# EPS.net
KiCad netlist of a schematic drawn in EAGLE
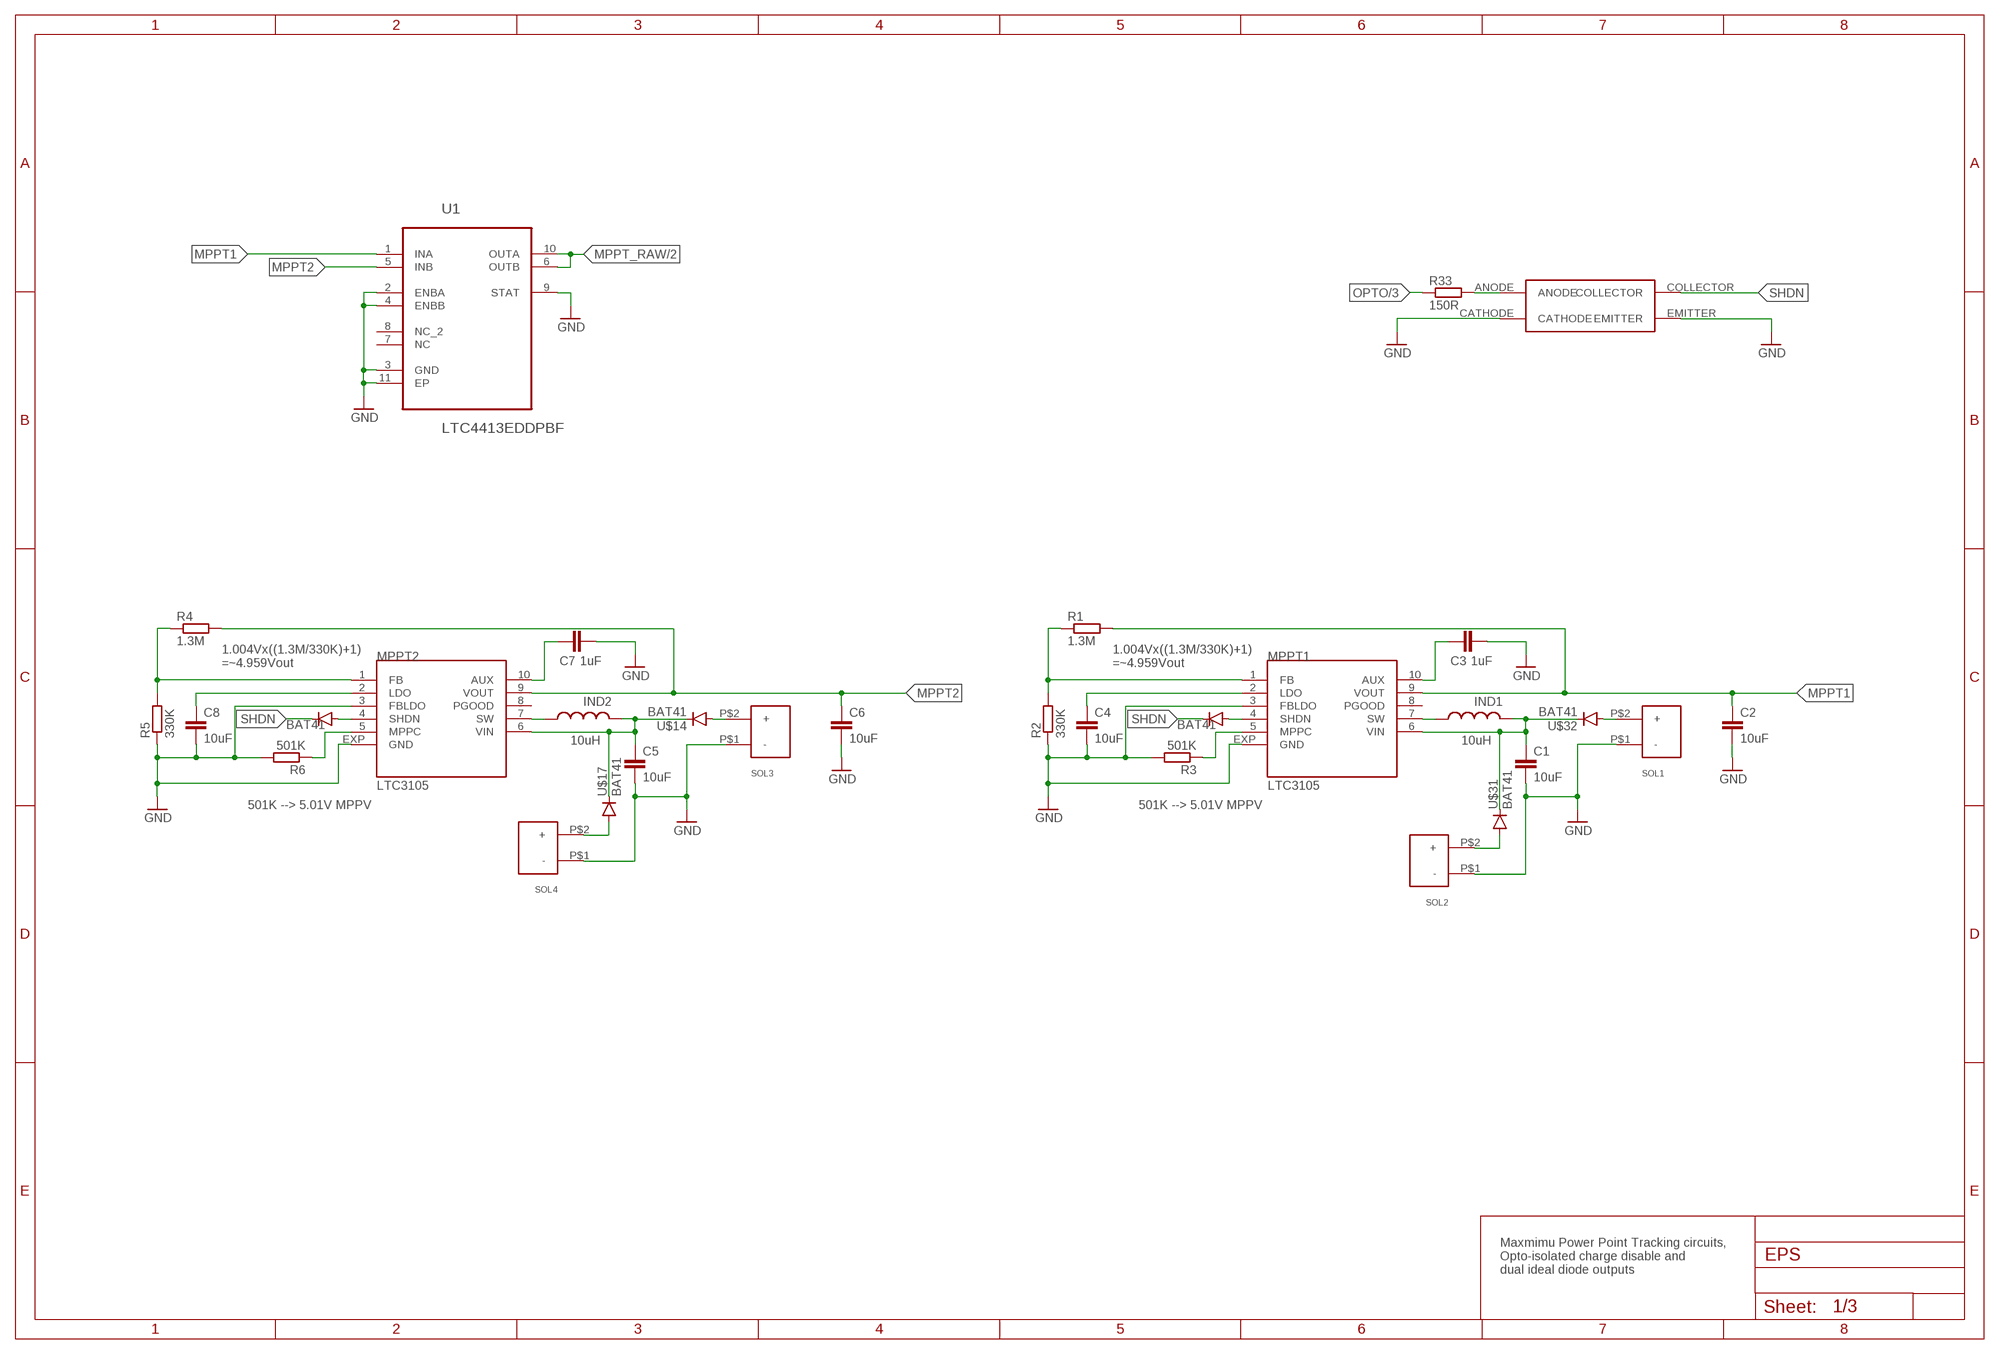
[diagram p0: schematic, sheet 1]
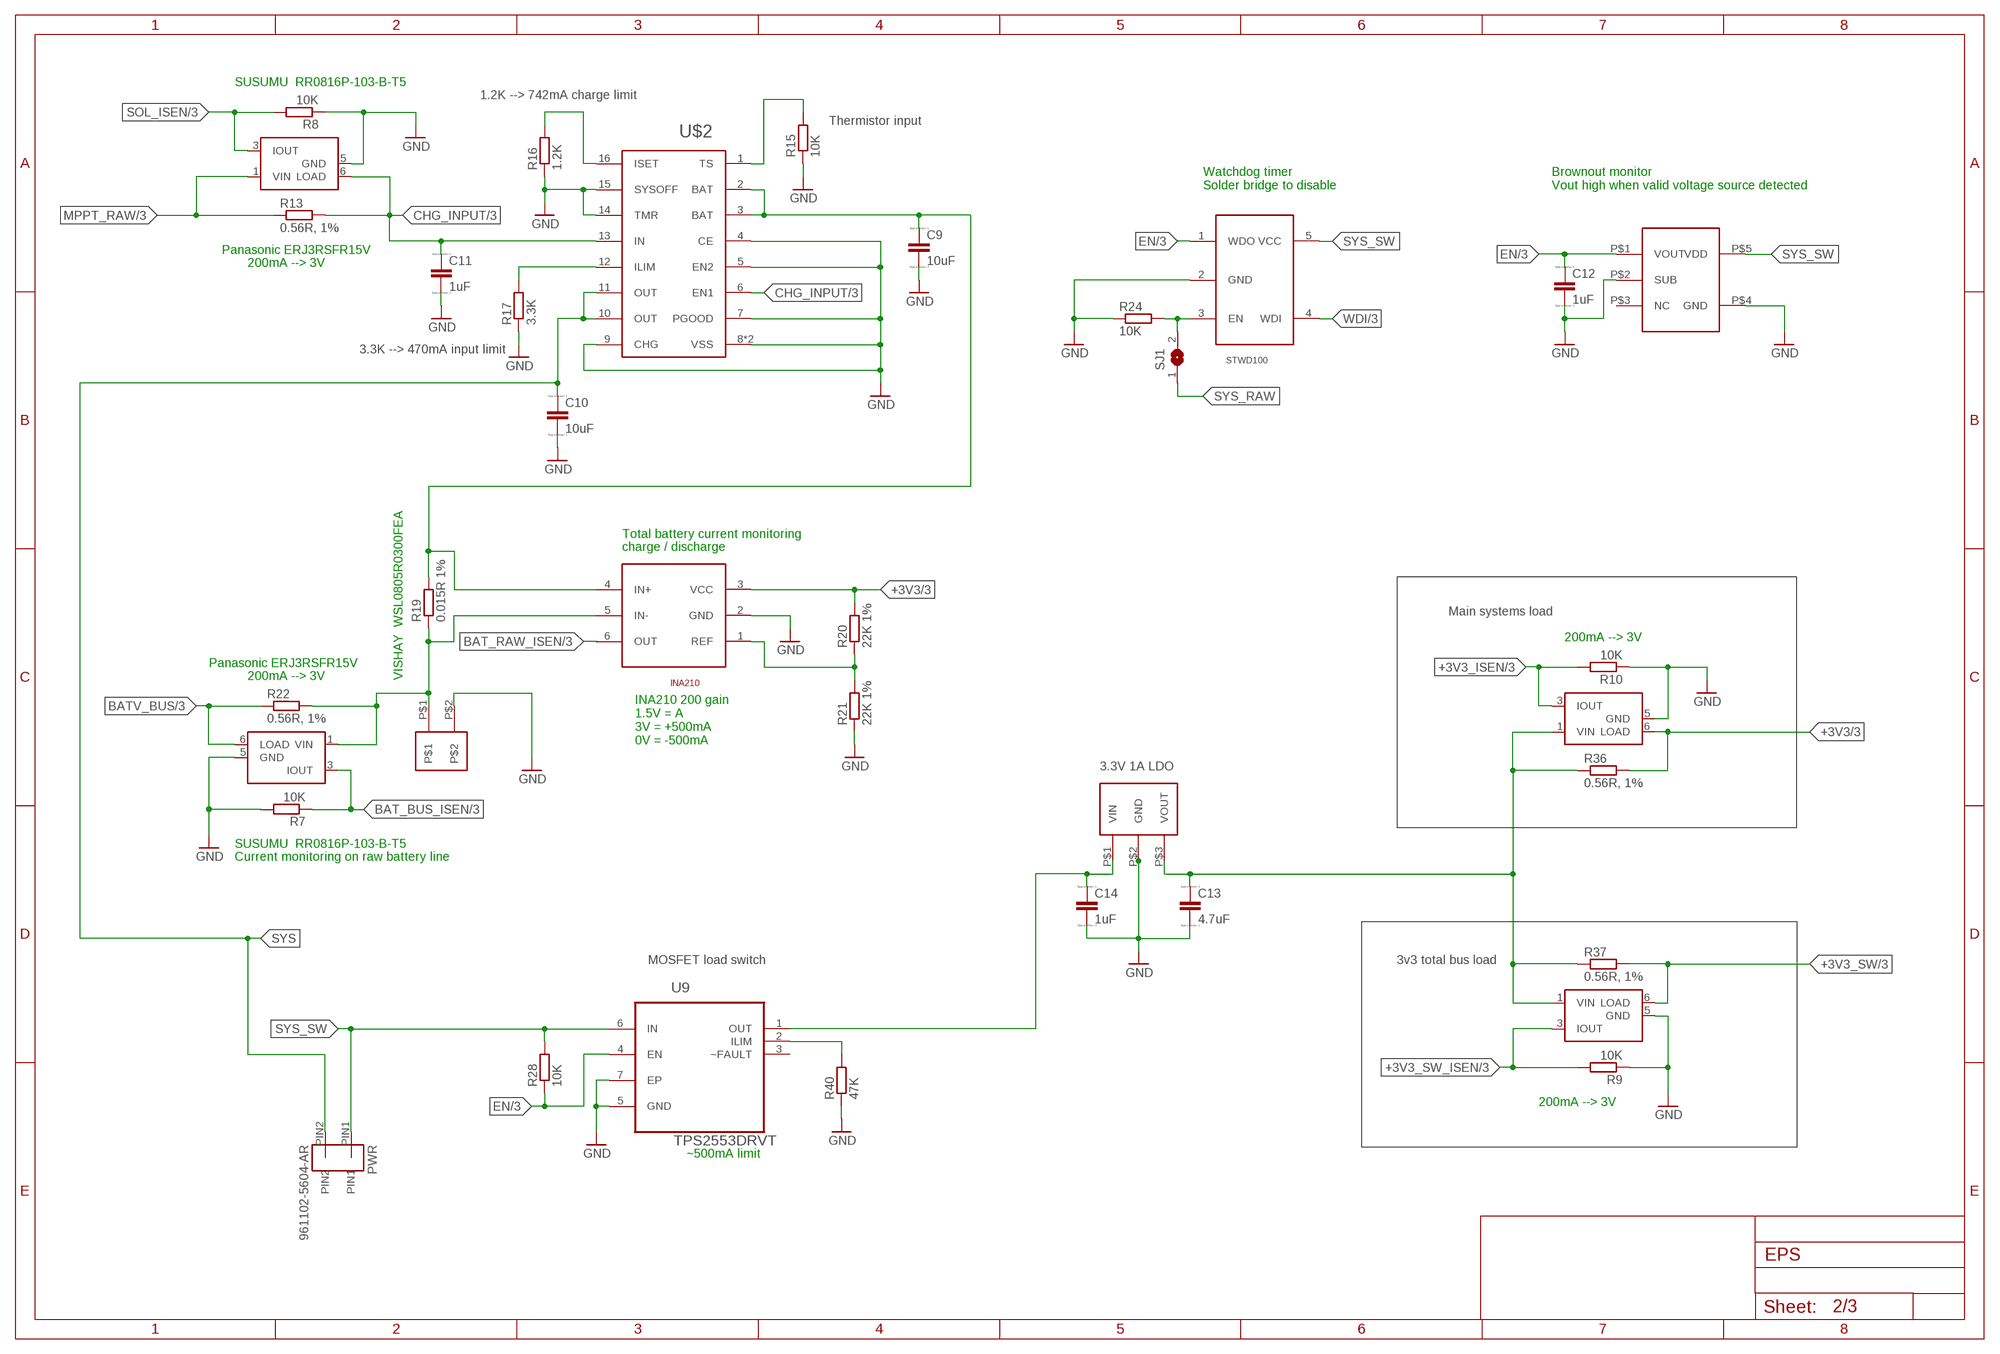
[diagram p1: schematic, sheet 2]
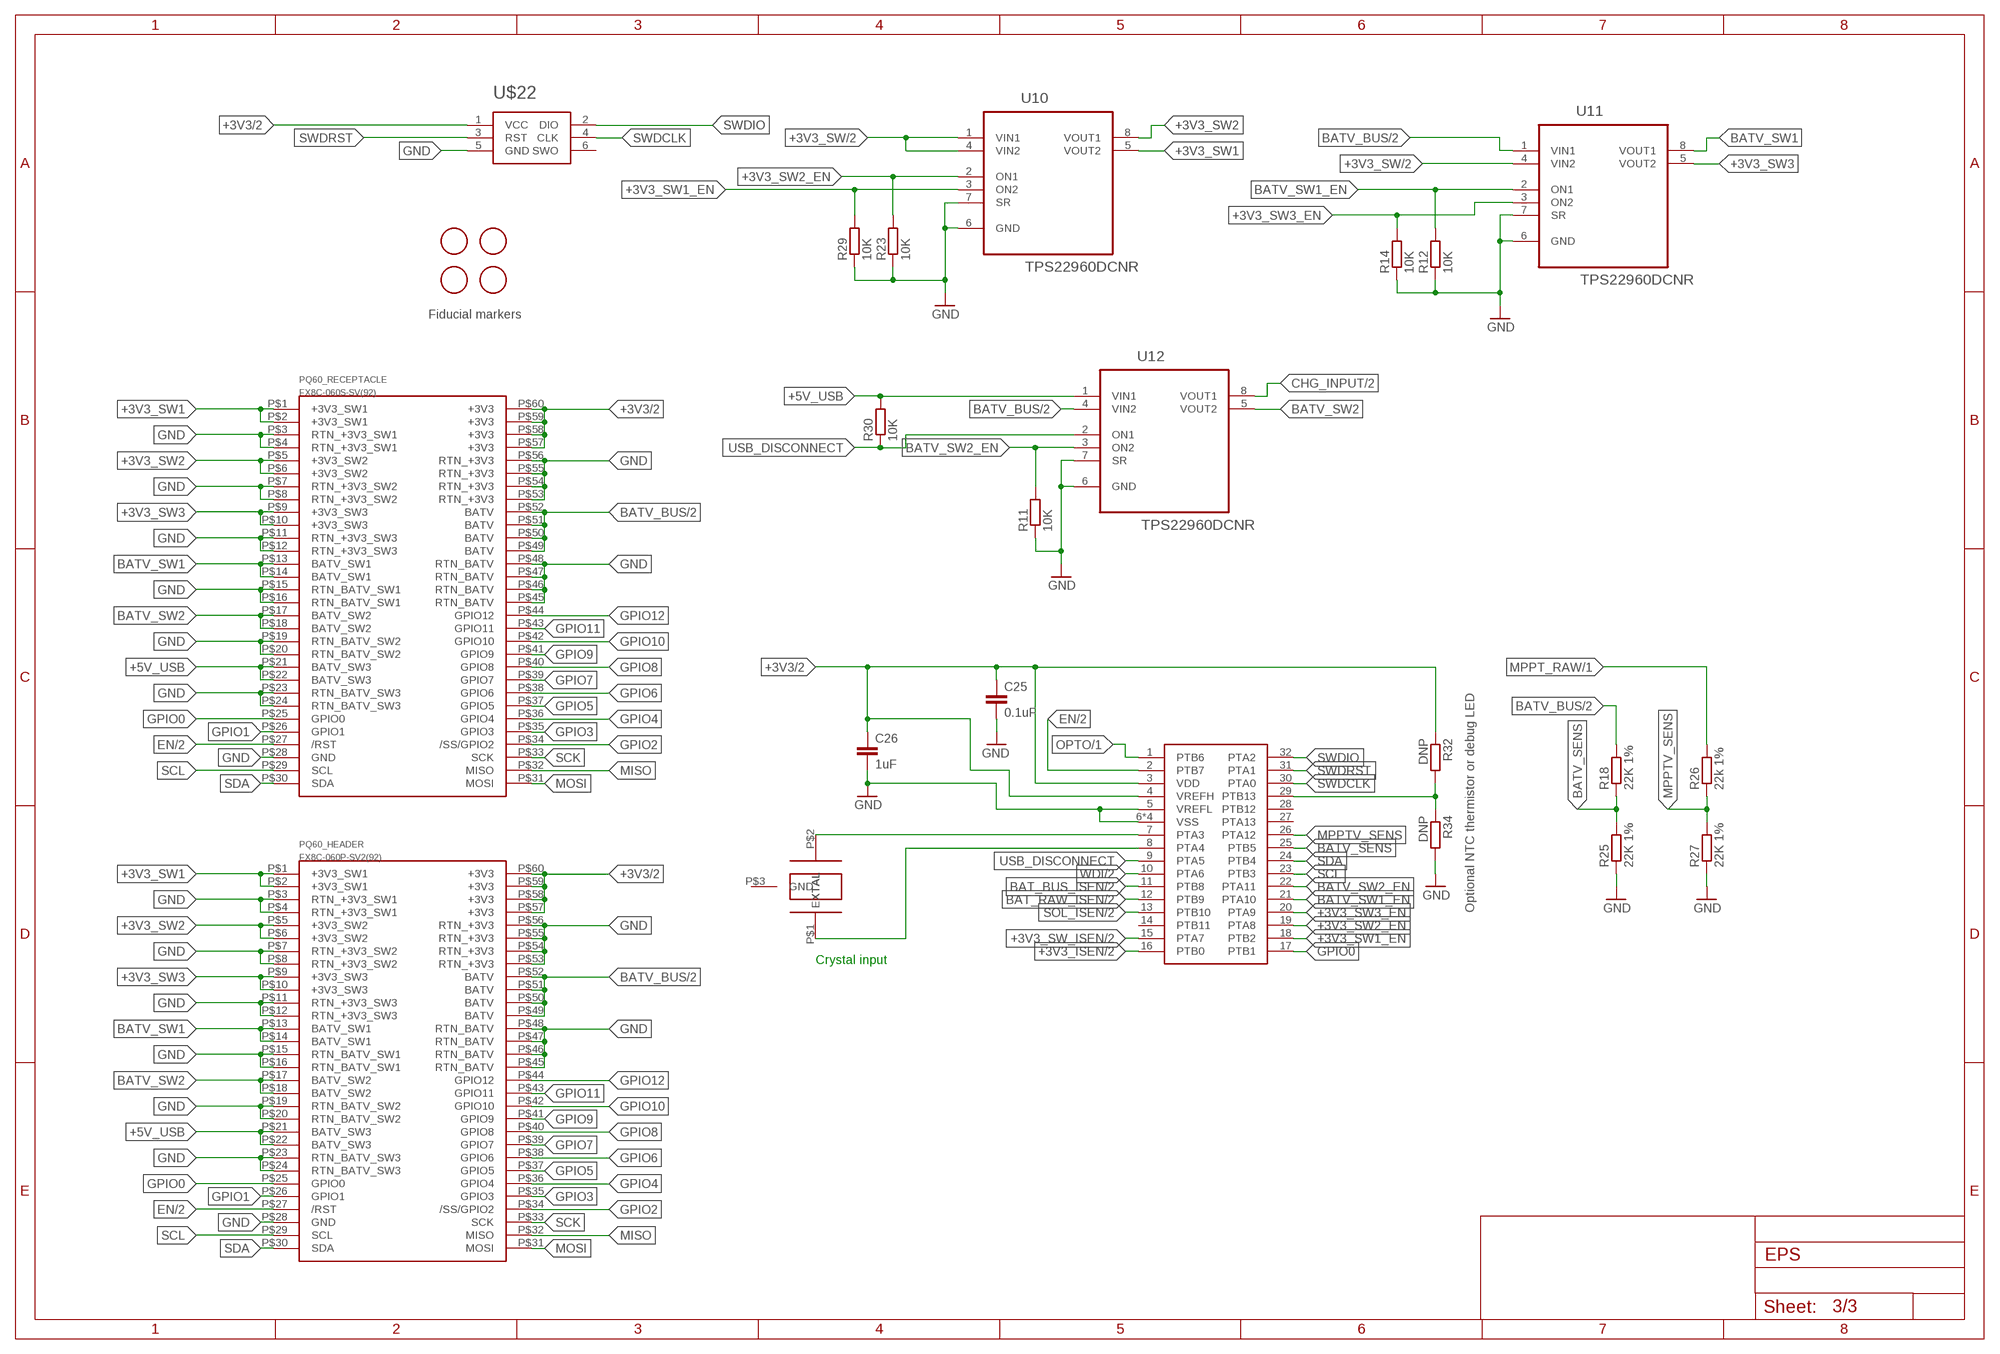
[diagram p2: schematic, sheet 3]

(export (version "E")
  (design (tool "Eeschema 10.0.6"))
  (components
    (comp (ref "C9")
      (value "10uF")
      (footprint "eagle-import:C0805")
      (libsource (lib "eagle-import") (part "C-EUC0805"))
    )
    (comp (ref "C10")
      (value "10uF")
      (footprint "eagle-import:C0805")
      (libsource (lib "eagle-import") (part "C-EUC0805"))
    )
    (comp (ref "C11")
      (value "1uF")
      (footprint "eagle-import:C0603")
      (libsource (lib "eagle-import") (part "C-EUC0603"))
    )
    (comp (ref "C12")
      (value "1uF")
      (footprint "eagle-import:C0603")
      (libsource (lib "eagle-import") (part "C-EUC0603"))
    )
    (comp (ref "C13")
      (value "4.7uF")
      (footprint "eagle-import:C0805")
      (libsource (lib "eagle-import") (part "C-EUC0805"))
    )
    (comp (ref "C14")
      (value "1uF")
      (footprint "eagle-import:C0603")
      (libsource (lib "eagle-import") (part "C-EUC0603"))
    )
    (comp (ref "INA210")
      (value "INA211A")
      (footprint "eagle-import:SC-70")
      (libsource (lib "eagle-import") (part "INA211A"))
    )
    (comp (ref "PWR")
      (value "961102-5604-AR")
      (footprint "eagle-import:961102-5604-AR")
      (libsource (lib "eagle-import") (part "961102-5604-AR"))
    )
    (comp (ref "R7")
      (value "10K")
      (footprint "eagle-import:R0402")
      (libsource (lib "eagle-import") (part "R-EU_R0402"))
    )
    (comp (ref "R8")
      (value "10K")
      (footprint "eagle-import:R0402")
      (libsource (lib "eagle-import") (part "R-EU_R0402"))
    )
    (comp (ref "R9")
      (value "10K")
      (footprint "eagle-import:R0402")
      (libsource (lib "eagle-import") (part "R-EU_R0402"))
    )
    (comp (ref "R10")
      (value "10K")
      (footprint "eagle-import:R0402")
      (libsource (lib "eagle-import") (part "R-EU_R0402"))
    )
    (comp (ref "R13")
      (value "0.56R, 1%")
      (footprint "eagle-import:R0603")
      (libsource (lib "eagle-import") (part "R-EU_R0603"))
    )
    (comp (ref "R15")
      (value "10K")
      (footprint "eagle-import:R0402")
      (libsource (lib "eagle-import") (part "R-EU_R0402"))
    )
    (comp (ref "R16")
      (value "1.2K")
      (footprint "eagle-import:R0402")
      (libsource (lib "eagle-import") (part "R-EU_R0402"))
    )
    (comp (ref "R17")
      (value "3.3K")
      (footprint "eagle-import:R0402")
      (libsource (lib "eagle-import") (part "R-EU_R0402"))
    )
    (comp (ref "R19")
      (value "0.015R 1%")
      (footprint "eagle-import:R0603")
      (libsource (lib "eagle-import") (part "R-EU_R0603"))
    )
    (comp (ref "R20")
      (value "22K 1%")
      (footprint "eagle-import:R0402")
      (libsource (lib "eagle-import") (part "R-EU_R0402"))
    )
    (comp (ref "R21")
      (value "22K 1%")
      (footprint "eagle-import:R0402")
      (libsource (lib "eagle-import") (part "R-EU_R0402"))
    )
    (comp (ref "R22")
      (value "0.56R, 1%")
      (footprint "eagle-import:R0603")
      (libsource (lib "eagle-import") (part "R-EU_R0603"))
    )
    (comp (ref "R24")
      (value "10K")
      (footprint "eagle-import:R0402")
      (libsource (lib "eagle-import") (part "R-EU_R0402"))
    )
    (comp (ref "R28")
      (value "10K")
      (footprint "eagle-import:R0402")
      (libsource (lib "eagle-import") (part "R-EU_R0402"))
    )
    (comp (ref "R36")
      (value "0.56R, 1%")
      (footprint "eagle-import:R0603")
      (libsource (lib "eagle-import") (part "R-EU_R0603"))
    )
    (comp (ref "R37")
      (value "0.56R, 1%")
      (footprint "eagle-import:R0603")
      (libsource (lib "eagle-import") (part "R-EU_R0603"))
    )
    (comp (ref "R40")
      (value "47K")
      (footprint "eagle-import:R0402")
      (libsource (lib "eagle-import") (part "R-EU_R0402"))
    )
    (comp (ref "SJ1") (value "SJ") (footprint "eagle-import:SJ") (libsource (lib "eagle-import") (part "SJ")))
    (comp (ref "STWD100")
      (value "STWD100PYW83F")
      (footprint "eagle-import:SOT_323-5")
      (libsource (lib "eagle-import") (part "STWD100PYW83F"))
    )
    (comp (ref "U$2")
      (value "BQ24079")
      (footprint "eagle-import:PVQFN16-THERM")
      (libsource (lib "eagle-import") (part "BQ24079"))
    )
    (comp (ref "U$3")
      (value "PICOBLADE53047")
      (footprint "eagle-import:PICOBLADE53047")
      (libsource (lib "eagle-import") (part "PICOBLADE53047"))
    )
    (comp (ref "U$18")
      (value "FAN4010IL6X_F113")
      (footprint "eagle-import:FAN4010IL6X_F113")
      (libsource (lib "eagle-import") (part "FAN4010IL6X_F113"))
    )
    (comp (ref "U$19")
      (value "FAN4010IL6X_F113")
      (footprint "eagle-import:FAN4010IL6X_F113")
      (libsource (lib "eagle-import") (part "FAN4010IL6X_F113"))
    )
    (comp (ref "U$20")
      (value "MCP1826S")
      (footprint "eagle-import:SOT223-3")
      (libsource (lib "eagle-import") (part "MCP1826S"))
    )
    (comp (ref "U$25")
      (value "FAN4010IL6X_F113")
      (footprint "eagle-import:FAN4010IL6X_F113")
      (libsource (lib "eagle-import") (part "FAN4010IL6X_F113"))
    )
    (comp (ref "U$26")
      (value "FAN4010IL6X_F113")
      (footprint "eagle-import:FAN4010IL6X_F113")
      (libsource (lib "eagle-import") (part "FAN4010IL6X_F113"))
    )
    (comp (ref "U$29")
      (value "BD4835FVE")
      (footprint "eagle-import:VSOF5")
      (libsource (lib "eagle-import") (part "BD4835FVE"))
    )
    (comp (ref "U9")
      (value "TPS2553DRVT")
      (footprint "eagle-import:SON65P200X200X80-7N")
      (libsource (lib "eagle-import") (part "TPS2553DRVT"))
    )
    (comp (ref "C25")
      (value "0.1uF")
      (footprint "eagle-import:C0402")
      (libsource (lib "eagle-import") (part "resistor_C-EUC0402"))
    )
    (comp (ref "C26")
      (value "1uF")
      (footprint "eagle-import:C0402")
      (libsource (lib "eagle-import") (part "resistor_C-EUC0402"))
    )
    (comp (ref "FD1")
      (value "FIDUCIAL")
      (footprint "eagle-import:FIDUCIAL_1MM")
      (libsource (lib "eagle-import") (part "FIDUCIAL"))
    )
    (comp (ref "FD2")
      (value "FIDUCIAL")
      (footprint "eagle-import:FIDUCIAL_1MM")
      (libsource (lib "eagle-import") (part "FIDUCIAL"))
    )
    (comp (ref "FD3")
      (value "FIDUCIAL")
      (footprint "eagle-import:FIDUCIAL_1MM")
      (libsource (lib "eagle-import") (part "FIDUCIAL"))
    )
    (comp (ref "FD4")
      (value "FIDUCIAL")
      (footprint "eagle-import:FIDUCIAL_1MM")
      (libsource (lib "eagle-import") (part "FIDUCIAL"))
    )
    (comp (ref "PQ60_HEADER")
      (value "FX8C-060P-SV2(92)")
      (footprint "eagle-import:FX8C-060P-SV(92)")
      (libsource (lib "eagle-import") (part "FX8C-060P-SV2(92)"))
    )
    (comp (ref "PQ60_RECEPTACLE")
      (value "FX8C-060S-SV(92)")
      (footprint "eagle-import:FX8C-060S-SV(92)")
      (libsource (lib "eagle-import") (part "FX8C-060S-SV(92)"))
    )
    (comp (ref "R11")
      (value "10K")
      (footprint "eagle-import:R0402")
      (libsource (lib "eagle-import") (part "R-EU_R0402"))
    )
    (comp (ref "R12")
      (value "10K")
      (footprint "eagle-import:R0402")
      (libsource (lib "eagle-import") (part "R-EU_R0402"))
    )
    (comp (ref "R14")
      (value "10K")
      (footprint "eagle-import:R0402")
      (libsource (lib "eagle-import") (part "R-EU_R0402"))
    )
    (comp (ref "R18")
      (value "22K 1%")
      (footprint "eagle-import:R0402")
      (libsource (lib "eagle-import") (part "R-EU_R0402"))
    )
    (comp (ref "R23")
      (value "10K")
      (footprint "eagle-import:R0402")
      (libsource (lib "eagle-import") (part "R-EU_R0402"))
    )
    (comp (ref "R25")
      (value "22K 1%")
      (footprint "eagle-import:R0402")
      (libsource (lib "eagle-import") (part "R-EU_R0402"))
    )
    (comp (ref "R26")
      (value "22k 1%")
      (footprint "eagle-import:R0402")
      (libsource (lib "eagle-import") (part "R-EU_R0402"))
    )
    (comp (ref "R27")
      (value "22K 1%")
      (footprint "eagle-import:R0402")
      (libsource (lib "eagle-import") (part "R-EU_R0402"))
    )
    (comp (ref "R29")
      (value "10K")
      (footprint "eagle-import:R0402")
      (libsource (lib "eagle-import") (part "R-EU_R0402"))
    )
    (comp (ref "R30")
      (value "10K")
      (footprint "eagle-import:R0402")
      (libsource (lib "eagle-import") (part "R-EU_R0402"))
    )
    (comp (ref "R32")
      (value "DNP")
      (footprint "eagle-import:R0402")
      (libsource (lib "eagle-import") (part "R-EU_R0402"))
    )
    (comp (ref "R34")
      (value "DNP")
      (footprint "eagle-import:R0402")
      (libsource (lib "eagle-import") (part "R-EU_R0402"))
    )
    (comp (ref "U$1")
      (value "AB26TRQ")
      (footprint "eagle-import:AB26TRQ")
      (libsource (lib "eagle-import") (part "AB26TRQ"))
    )
    (comp (ref "U$21")
      (value "MKL02Z16VFM4")
      (footprint "eagle-import:MKL02Z16VFM4")
      (libsource (lib "eagle-import") (part "MKL02Z16VFM4"))
    )
    (comp (ref "U$22")
      (value "TAG_CONNECT_NO_HOLES")
      (footprint "eagle-import:TAG_CONNECT_NO_HOLES")
      (libsource (lib "eagle-import") (part "TAG_CONNECT_NO_HOLES"))
    )
    (comp (ref "U10")
      (value "TPS22960DCNR")
      (footprint "eagle-import:SOT65P280X145-8N")
      (libsource (lib "eagle-import") (part "TPS22960DCNR"))
    )
    (comp (ref "U11")
      (value "TPS22960DCNR")
      (footprint "eagle-import:SOT65P280X145-8N")
      (libsource (lib "eagle-import") (part "TPS22960DCNR"))
    )
    (comp (ref "U12")
      (value "TPS22960DCNR")
      (footprint "eagle-import:SOT65P280X145-8N")
      (libsource (lib "eagle-import") (part "TPS22960DCNR"))
    )
    (comp (ref "C1")
      (value "10uF")
      (footprint "eagle-import:C0603")
      (libsource (lib "eagle-import") (part "resistor_C-EUC0603"))
    )
    (comp (ref "C2")
      (value "10uF")
      (footprint "eagle-import:C0603")
      (libsource (lib "eagle-import") (part "resistor_C-EUC0603"))
    )
    (comp (ref "C3")
      (value "1uF")
      (footprint "eagle-import:C0402")
      (libsource (lib "eagle-import") (part "resistor_C-EUC0402"))
    )
    (comp (ref "C4")
      (value "10uF")
      (footprint "eagle-import:C0603")
      (libsource (lib "eagle-import") (part "resistor_C-EUC0603"))
    )
    (comp (ref "C5")
      (value "10uF")
      (footprint "eagle-import:C0603")
      (libsource (lib "eagle-import") (part "resistor_C-EUC0603"))
    )
    (comp (ref "C6")
      (value "10uF")
      (footprint "eagle-import:C0603")
      (libsource (lib "eagle-import") (part "resistor_C-EUC0603"))
    )
    (comp (ref "C7")
      (value "1uF")
      (footprint "eagle-import:C0402")
      (libsource (lib "eagle-import") (part "resistor_C-EUC0402"))
    )
    (comp (ref "C8")
      (value "10uF")
      (footprint "eagle-import:C0603")
      (libsource (lib "eagle-import") (part "resistor_C-EUC0603"))
    )
    (comp (ref "IND1")
      (value "WE-TPC-744031100")
      (footprint "eagle-import:WE-TPC-744031100")
      (libsource (lib "eagle-import") (part "WE-TPC-744031100"))
    )
    (comp (ref "IND2")
      (value "WE-TPC-744031100")
      (footprint "eagle-import:WE-TPC-744031100")
      (libsource (lib "eagle-import") (part "WE-TPC-744031100"))
    )
    (comp (ref "MPPT1")
      (value "LTC3105")
      (footprint "eagle-import:DFN-3X3")
      (libsource (lib "eagle-import") (part "LTC3105"))
    )
    (comp (ref "MPPT2")
      (value "LTC3105")
      (footprint "eagle-import:DFN-3X3")
      (libsource (lib "eagle-import") (part "LTC3105"))
    )
    (comp (ref "R1")
      (value "1.3M")
      (footprint "eagle-import:R0402")
      (libsource (lib "eagle-import") (part "R-EU_R0402"))
    )
    (comp (ref "R2")
      (value "330K")
      (footprint "eagle-import:R0402")
      (libsource (lib "eagle-import") (part "R-EU_R0402"))
    )
    (comp (ref "R3")
      (value "501K")
      (footprint "eagle-import:R0402")
      (libsource (lib "eagle-import") (part "R-EU_R0402"))
    )
    (comp (ref "R4")
      (value "1.3M")
      (footprint "eagle-import:R0402")
      (libsource (lib "eagle-import") (part "R-EU_R0402"))
    )
    (comp (ref "R5")
      (value "330K")
      (footprint "eagle-import:R0402")
      (libsource (lib "eagle-import") (part "R-EU_R0402"))
    )
    (comp (ref "R6")
      (value "501K")
      (footprint "eagle-import:R0402")
      (libsource (lib "eagle-import") (part "R-EU_R0402"))
    )
    (comp (ref "R33")
      (value "150R")
      (footprint "eagle-import:R0402")
      (libsource (lib "eagle-import") (part "R-EU_R0402"))
    )
    (comp (ref "SOL1")
      (value "JST-B2B-ZH")
      (footprint "eagle-import:JST-B2B-ZR")
      (libsource (lib "eagle-import") (part "JST-B2B-ZH"))
    )
    (comp (ref "SOL2")
      (value "JST-B2B-ZH")
      (footprint "eagle-import:JST-B2B-ZR")
      (libsource (lib "eagle-import") (part "JST-B2B-ZH"))
    )
    (comp (ref "SOL3")
      (value "JST-B2B-ZH")
      (footprint "eagle-import:JST-B2B-ZR")
      (libsource (lib "eagle-import") (part "JST-B2B-ZH"))
    )
    (comp (ref "SOL4")
      (value "JST-B2B-ZH")
      (footprint "eagle-import:JST-B2B-ZR")
      (libsource (lib "eagle-import") (part "JST-B2B-ZH"))
    )
    (comp (ref "U$4")
      (value "BAT41")
      (footprint "eagle-import:SOD-123")
      (libsource (lib "eagle-import") (part "BAT41"))
    )
    (comp (ref "U$10")
      (value "BAT41")
      (footprint "eagle-import:SOD-123")
      (libsource (lib "eagle-import") (part "BAT41"))
    )
    (comp (ref "U$14")
      (value "BAT41")
      (footprint "eagle-import:SOD-123")
      (libsource (lib "eagle-import") (part "BAT41"))
    )
    (comp (ref "U$17")
      (value "BAT41")
      (footprint "eagle-import:SOD-123")
      (libsource (lib "eagle-import") (part "BAT41"))
    )
    (comp (ref "U$24")
      (value "EL3H7")
      (footprint "eagle-import:EL3H7")
      (libsource (lib "eagle-import") (part "EL3H7"))
    )
    (comp (ref "U$31")
      (value "BAT41")
      (footprint "eagle-import:SOD-123")
      (libsource (lib "eagle-import") (part "BAT41"))
    )
    (comp (ref "U$32")
      (value "BAT41")
      (footprint "eagle-import:SOD-123")
      (libsource (lib "eagle-import") (part "BAT41"))
    )
    (comp (ref "U1")
      (value "LTC4413EDDPBF")
      (footprint "eagle-import:DFN300X300X80-11N")
      (fields (field (name "MPN") "LTC4413EDD#PBF"))
      (libsource (lib "eagle-import") (part "LTC4413EDDPBF"))
    )
  )
  (nets
    (net (code "1") (name "+3V3") (class "Default")
      (node (ref "C25") (pin "1") (pinfunction "1_1") (pintype "passive"))
      (node (ref "C26") (pin "1") (pinfunction "1_1") (pintype "passive"))
      (node (ref "INA210") (pin "3") (pinfunction "VCC_3") (pintype "bidirectional"))
      (node (ref "PQ60_HEADER") (pin "P$57") (pinfunction "+3V3_P$57") (pintype "power_in"))
      (node (ref "PQ60_HEADER") (pin "P$58") (pinfunction "+3V3_P$58") (pintype "power_in"))
      (node (ref "PQ60_HEADER") (pin "P$59") (pinfunction "+3V3_P$59") (pintype "power_in"))
      (node (ref "PQ60_HEADER") (pin "P$60") (pinfunction "+3V3_P$60") (pintype "power_in"))
      (node (ref "PQ60_RECEPTACLE") (pin "P$57") (pinfunction "+3V3_P$57") (pintype "power_in"))
      (node (ref "PQ60_RECEPTACLE") (pin "P$58") (pinfunction "+3V3_P$58") (pintype "power_in"))
      (node (ref "PQ60_RECEPTACLE") (pin "P$59") (pinfunction "+3V3_P$59") (pintype "power_in"))
      (node (ref "PQ60_RECEPTACLE") (pin "P$60") (pinfunction "+3V3_P$60") (pintype "power_in"))
      (node (ref "R20") (pin "2") (pinfunction "2_2") (pintype "passive"))
      (node (ref "R32") (pin "1") (pinfunction "1_1") (pintype "passive"))
      (node (ref "R36") (pin "2") (pinfunction "2_2") (pintype "passive"))
      (node (ref "U$21") (pin "3") (pinfunction "VDD_3") (pintype "bidirectional"))
      (node (ref "U$21") (pin "4") (pinfunction "VREFH_4") (pintype "bidirectional"))
      (node (ref "U$22") (pin "1") (pinfunction "VCC_1") (pintype "bidirectional"))
      (node (ref "U$25") (pin "6") (pinfunction "LOAD_6") (pintype "bidirectional"))
    )
    (net (code "2") (name "+3V3_ISEN") (class "Default")
      (node (ref "R10") (pin "2") (pinfunction "2_2") (pintype "passive"))
      (node (ref "U$21") (pin "16") (pinfunction "PTB0_16") (pintype "bidirectional"))
      (node (ref "U$25") (pin "3") (pinfunction "IOUT_3") (pintype "bidirectional"))
    )
    (net (code "3") (name "+3V3_SW") (class "Default")
      (node (ref "R37") (pin "2") (pinfunction "2_2") (pintype "passive"))
      (node (ref "U$26") (pin "6") (pinfunction "LOAD_6") (pintype "bidirectional"))
      (node (ref "U10") (pin "1") (pinfunction "VIN1_1") (pintype "power_in"))
      (node (ref "U10") (pin "4") (pinfunction "VIN2_4") (pintype "power_in"))
      (node (ref "U11") (pin "4") (pinfunction "VIN2_4") (pintype "power_in"))
    )
    (net (code "4") (name "+3V3_SW1") (class "Default")
      (node (ref "PQ60_HEADER") (pin "P$1") (pinfunction "+3V3_SW1_P$1") (pintype "power_in"))
      (node (ref "PQ60_HEADER") (pin "P$2") (pinfunction "+3V3_SW1_P$2") (pintype "power_in"))
      (node (ref "PQ60_RECEPTACLE") (pin "P$1") (pinfunction "+3V3_SW1_P$1") (pintype "power_in"))
      (node (ref "PQ60_RECEPTACLE") (pin "P$2") (pinfunction "+3V3_SW1_P$2") (pintype "power_in"))
      (node (ref "U10") (pin "5") (pinfunction "VOUT2_5") (pintype "output"))
    )
    (net (code "5") (name "+3V3_SW1_EN") (class "Default")
      (node (ref "R29") (pin "2") (pinfunction "2_2") (pintype "passive"))
      (node (ref "U$21") (pin "18") (pinfunction "PTB2_18") (pintype "bidirectional"))
      (node (ref "U10") (pin "3") (pinfunction "ON2_3") (pintype "input"))
    )
    (net (code "6") (name "+3V3_SW2") (class "Default")
      (node (ref "PQ60_HEADER") (pin "P$5") (pinfunction "+3V3_SW2_P$5") (pintype "power_in"))
      (node (ref "PQ60_HEADER") (pin "P$6") (pinfunction "+3V3_SW2_P$6") (pintype "power_in"))
      (node (ref "PQ60_RECEPTACLE") (pin "P$5") (pinfunction "+3V3_SW2_P$5") (pintype "power_in"))
      (node (ref "PQ60_RECEPTACLE") (pin "P$6") (pinfunction "+3V3_SW2_P$6") (pintype "power_in"))
      (node (ref "U10") (pin "8") (pinfunction "VOUT1_8") (pintype "output"))
    )
    (net (code "7") (name "+3V3_SW2_EN") (class "Default")
      (node (ref "R23") (pin "2") (pinfunction "2_2") (pintype "passive"))
      (node (ref "U$21") (pin "19") (pinfunction "PTA8_19") (pintype "bidirectional"))
      (node (ref "U10") (pin "2") (pinfunction "ON1_2") (pintype "input"))
    )
    (net (code "8") (name "+3V3_SW3") (class "Default")
      (node (ref "PQ60_HEADER") (pin "P$10") (pinfunction "+3V3_SW3_P$10") (pintype "power_in"))
      (node (ref "PQ60_HEADER") (pin "P$9") (pinfunction "+3V3_SW3_P$9") (pintype "power_in"))
      (node (ref "PQ60_RECEPTACLE") (pin "P$10") (pinfunction "+3V3_SW3_P$10") (pintype "power_in"))
      (node (ref "PQ60_RECEPTACLE") (pin "P$9") (pinfunction "+3V3_SW3_P$9") (pintype "power_in"))
      (node (ref "U11") (pin "5") (pinfunction "VOUT2_5") (pintype "output"))
    )
    (net (code "9") (name "+3V3_SW3_EN") (class "Default")
      (node (ref "R14") (pin "2") (pinfunction "2_2") (pintype "passive"))
      (node (ref "U$21") (pin "20") (pinfunction "PTA9_20") (pintype "bidirectional"))
      (node (ref "U11") (pin "3") (pinfunction "ON2_3") (pintype "input"))
    )
    (net (code "10") (name "+3V3_SW_ISEN") (class "Default")
      (node (ref "R9") (pin "2") (pinfunction "2_2") (pintype "passive"))
      (node (ref "U$21") (pin "15") (pinfunction "PTA7_15") (pintype "bidirectional"))
      (node (ref "U$26") (pin "3") (pinfunction "IOUT_3") (pintype "bidirectional"))
    )
    (net (code "11") (name "+5V_USB") (class "Default")
      (node (ref "PQ60_HEADER") (pin "P$21") (pinfunction "BATV_SW3_P$21") (pintype "power_in"))
      (node (ref "PQ60_HEADER") (pin "P$22") (pinfunction "BATV_SW3_P$22") (pintype "power_in"))
      (node (ref "PQ60_RECEPTACLE") (pin "P$21") (pinfunction "BATV_SW3_P$21") (pintype "power_in"))
      (node (ref "PQ60_RECEPTACLE") (pin "P$22") (pinfunction "BATV_SW3_P$22") (pintype "power_in"))
      (node (ref "R30") (pin "2") (pinfunction "2_2") (pintype "passive"))
      (node (ref "U12") (pin "1") (pinfunction "VIN1_1") (pintype "power_in"))
    )
    (net (code "12") (name "BATV_BUS") (class "Default")
      (node (ref "PQ60_HEADER") (pin "P$49") (pinfunction "BATV_P$49") (pintype "power_in"))
      (node (ref "PQ60_HEADER") (pin "P$50") (pinfunction "BATV_P$50") (pintype "power_in"))
      (node (ref "PQ60_HEADER") (pin "P$51") (pinfunction "BATV_P$51") (pintype "power_in"))
      (node (ref "PQ60_HEADER") (pin "P$52") (pinfunction "BATV_P$52") (pintype "power_in"))
      (node (ref "PQ60_RECEPTACLE") (pin "P$49") (pinfunction "BATV_P$49") (pintype "power_in"))
      (node (ref "PQ60_RECEPTACLE") (pin "P$50") (pinfunction "BATV_P$50") (pintype "power_in"))
      (node (ref "PQ60_RECEPTACLE") (pin "P$51") (pinfunction "BATV_P$51") (pintype "power_in"))
      (node (ref "PQ60_RECEPTACLE") (pin "P$52") (pinfunction "BATV_P$52") (pintype "power_in"))
      (node (ref "R18") (pin "2") (pinfunction "2_2") (pintype "passive"))
      (node (ref "R22") (pin "1") (pinfunction "1_1") (pintype "passive"))
      (node (ref "U$19") (pin "6") (pinfunction "LOAD_6") (pintype "bidirectional"))
      (node (ref "U11") (pin "1") (pinfunction "VIN1_1") (pintype "power_in"))
      (node (ref "U12") (pin "4") (pinfunction "VIN2_4") (pintype "power_in"))
    )
    (net (code "13") (name "BATV_SENS") (class "Default")
      (node (ref "R18") (pin "1") (pinfunction "1_1") (pintype "passive"))
      (node (ref "R25") (pin "2") (pinfunction "2_2") (pintype "passive"))
      (node (ref "U$21") (pin "25") (pinfunction "PTB5_25") (pintype "bidirectional"))
    )
    (net (code "14") (name "BATV_SW1") (class "Default")
      (node (ref "PQ60_HEADER") (pin "P$13") (pinfunction "BATV_SW1_P$13") (pintype "power_in"))
      (node (ref "PQ60_HEADER") (pin "P$14") (pinfunction "BATV_SW1_P$14") (pintype "power_in"))
      (node (ref "PQ60_RECEPTACLE") (pin "P$13") (pinfunction "BATV_SW1_P$13") (pintype "power_in"))
      (node (ref "PQ60_RECEPTACLE") (pin "P$14") (pinfunction "BATV_SW1_P$14") (pintype "power_in"))
      (node (ref "U11") (pin "8") (pinfunction "VOUT1_8") (pintype "output"))
    )
    (net (code "15") (name "BATV_SW1_EN") (class "Default")
      (node (ref "R12") (pin "2") (pinfunction "2_2") (pintype "passive"))
      (node (ref "U$21") (pin "21") (pinfunction "PTA10_21") (pintype "bidirectional"))
      (node (ref "U11") (pin "2") (pinfunction "ON1_2") (pintype "input"))
    )
    (net (code "16") (name "BATV_SW2") (class "Default")
      (node (ref "PQ60_HEADER") (pin "P$17") (pinfunction "BATV_SW2_P$17") (pintype "power_in"))
      (node (ref "PQ60_HEADER") (pin "P$18") (pinfunction "BATV_SW2_P$18") (pintype "power_in"))
      (node (ref "PQ60_RECEPTACLE") (pin "P$17") (pinfunction "BATV_SW2_P$17") (pintype "power_in"))
      (node (ref "PQ60_RECEPTACLE") (pin "P$18") (pinfunction "BATV_SW2_P$18") (pintype "power_in"))
      (node (ref "U12") (pin "5") (pinfunction "VOUT2_5") (pintype "output"))
    )
    (net (code "17") (name "BATV_SW2_EN") (class "Default")
      (node (ref "R11") (pin "2") (pinfunction "2_2") (pintype "passive"))
      (node (ref "U$21") (pin "22") (pinfunction "PTA11_22") (pintype "bidirectional"))
      (node (ref "U12") (pin "3") (pinfunction "ON2_3") (pintype "input"))
    )
    (net (code "18") (name "BAT_BUS_ISEN") (class "Default")
      (node (ref "R7") (pin "1") (pinfunction "1_1") (pintype "passive"))
      (node (ref "U$19") (pin "3") (pinfunction "IOUT_3") (pintype "bidirectional"))
      (node (ref "U$21") (pin "11") (pinfunction "PTB8_11") (pintype "bidirectional"))
    )
    (net (code "19") (name "BAT_RAW_ISEN") (class "Default")
      (node (ref "INA210") (pin "6") (pinfunction "OUT_6") (pintype "bidirectional"))
      (node (ref "U$21") (pin "12") (pinfunction "PTB9_12") (pintype "bidirectional"))
    )
    (net (code "20") (name "CHG_INPUT") (class "Default")
      (node (ref "C11") (pin "1") (pinfunction "1_1") (pintype "passive"))
      (node (ref "R13") (pin "2") (pinfunction "2_2") (pintype "passive"))
      (node (ref "U$18") (pin "6") (pinfunction "LOAD_6") (pintype "bidirectional"))
      (node (ref "U$2") (pin "13") (pinfunction "IN_13") (pintype "bidirectional"))
      (node (ref "U$2") (pin "6") (pinfunction "EN1_6") (pintype "bidirectional"))
      (node (ref "U12") (pin "8") (pinfunction "VOUT1_8") (pintype "output"))
    )
    (net (code "21") (name "EN") (class "Default")
      (node (ref "C12") (pin "1") (pinfunction "1_1") (pintype "passive"))
      (node (ref "PQ60_HEADER") (pin "P$27") (pinfunction "/RST_P$27") (pintype "bidirectional"))
      (node (ref "PQ60_RECEPTACLE") (pin "P$27") (pinfunction "/RST_P$27") (pintype "bidirectional"))
      (node (ref "R28") (pin "1") (pinfunction "1_1") (pintype "passive"))
      (node (ref "STWD100") (pin "1") (pinfunction "WDO_1") (pintype "bidirectional"))
      (node (ref "U$21") (pin "2") (pinfunction "PTB7_2") (pintype "bidirectional"))
      (node (ref "U$29") (pin "P$1") (pinfunction "VOUT_P$1") (pintype "bidirectional"))
      (node (ref "U9") (pin "4") (pinfunction "EN_4") (pintype "input"))
    )
    (net (code "22") (name "GND") (class "Default")
      (node (ref "C1") (pin "2") (pinfunction "2_2") (pintype "passive"))
      (node (ref "C10") (pin "2") (pinfunction "2_2") (pintype "passive"))
      (node (ref "C11") (pin "2") (pinfunction "2_2") (pintype "passive"))
      (node (ref "C12") (pin "2") (pinfunction "2_2") (pintype "passive"))
      (node (ref "C13") (pin "2") (pinfunction "2_2") (pintype "passive"))
      (node (ref "C14") (pin "2") (pinfunction "2_2") (pintype "passive"))
      (node (ref "C2") (pin "2") (pinfunction "2_2") (pintype "passive"))
      (node (ref "C25") (pin "2") (pinfunction "2_2") (pintype "passive"))
      (node (ref "C26") (pin "2") (pinfunction "2_2") (pintype "passive"))
      (node (ref "C3") (pin "2") (pinfunction "2_2") (pintype "passive"))
      (node (ref "C4") (pin "2") (pinfunction "2_2") (pintype "passive"))
      (node (ref "C5") (pin "2") (pinfunction "2_2") (pintype "passive"))
      (node (ref "C6") (pin "2") (pinfunction "2_2") (pintype "passive"))
      (node (ref "C7") (pin "2") (pinfunction "2_2") (pintype "passive"))
      (node (ref "C8") (pin "2") (pinfunction "2_2") (pintype "passive"))
      (node (ref "C9") (pin "2") (pinfunction "2_2") (pintype "passive"))
      (node (ref "INA210") (pin "2") (pinfunction "GND_2") (pintype "bidirectional"))
      (node (ref "MPPT1") (pin "3") (pinfunction "FBLDO_3") (pintype "power_in"))
      (node (ref "MPPT1") (pin "EXP") (pinfunction "GND_EXP") (pintype "power_in"))
      (node (ref "MPPT2") (pin "3") (pinfunction "FBLDO_3") (pintype "power_in"))
      (node (ref "MPPT2") (pin "EXP") (pinfunction "GND_EXP") (pintype "power_in"))
      (node (ref "PQ60_HEADER") (pin "P$11") (pinfunction "RTN_+3V3_SW3_P$11") (pintype "power_in"))
      (node (ref "PQ60_HEADER") (pin "P$12") (pinfunction "RTN_+3V3_SW3_P$12") (pintype "power_in"))
      (node (ref "PQ60_HEADER") (pin "P$15") (pinfunction "RTN_BATV_SW1_P$15") (pintype "power_in"))
      (node (ref "PQ60_HEADER") (pin "P$16") (pinfunction "RTN_BATV_SW1_P$16") (pintype "power_in"))
      (node (ref "PQ60_HEADER") (pin "P$19") (pinfunction "RTN_BATV_SW2_P$19") (pintype "power_in"))
      (node (ref "PQ60_HEADER") (pin "P$20") (pinfunction "RTN_BATV_SW2_P$20") (pintype "power_in"))
      (node (ref "PQ60_HEADER") (pin "P$23") (pinfunction "RTN_BATV_SW3_P$23") (pintype "power_in"))
      (node (ref "PQ60_HEADER") (pin "P$24") (pinfunction "RTN_BATV_SW3_P$24") (pintype "power_in"))
      (node (ref "PQ60_HEADER") (pin "P$28") (pinfunction "GND_P$28") (pintype "bidirectional"))
      (node (ref "PQ60_HEADER") (pin "P$3") (pinfunction "RTN_+3V3_SW1_P$3") (pintype "power_in"))
      (node (ref "PQ60_HEADER") (pin "P$4") (pinfunction "RTN_+3V3_SW1_P$4") (pintype "power_in"))
      (node (ref "PQ60_HEADER") (pin "P$45") (pinfunction "RTN_BATV_P$45") (pintype "power_in"))
      (node (ref "PQ60_HEADER") (pin "P$46") (pinfunction "RTN_BATV_P$46") (pintype "power_in"))
      (node (ref "PQ60_HEADER") (pin "P$47") (pinfunction "RTN_BATV_P$47") (pintype "power_in"))
      (node (ref "PQ60_HEADER") (pin "P$48") (pinfunction "RTN_BATV_P$48") (pintype "power_in"))
      (node (ref "PQ60_HEADER") (pin "P$53") (pinfunction "RTN_+3V3_P$53") (pintype "power_in"))
      (node (ref "PQ60_HEADER") (pin "P$54") (pinfunction "RTN_+3V3_P$54") (pintype "power_in"))
      (node (ref "PQ60_HEADER") (pin "P$55") (pinfunction "RTN_+3V3_P$55") (pintype "power_in"))
      (node (ref "PQ60_HEADER") (pin "P$56") (pinfunction "RTN_+3V3_P$56") (pintype "power_in"))
      (node (ref "PQ60_HEADER") (pin "P$7") (pinfunction "RTN_+3V3_SW2_P$7") (pintype "power_in"))
      (node (ref "PQ60_HEADER") (pin "P$8") (pinfunction "RTN_+3V3_SW2_P$8") (pintype "power_in"))
      (node (ref "PQ60_RECEPTACLE") (pin "P$11") (pinfunction "RTN_+3V3_SW3_P$11") (pintype "power_in"))
      (node (ref "PQ60_RECEPTACLE") (pin "P$12") (pinfunction "RTN_+3V3_SW3_P$12") (pintype "power_in"))
      (node (ref "PQ60_RECEPTACLE") (pin "P$15") (pinfunction "RTN_BATV_SW1_P$15") (pintype "power_in"))
      (node (ref "PQ60_RECEPTACLE") (pin "P$16") (pinfunction "RTN_BATV_SW1_P$16") (pintype "power_in"))
      (node (ref "PQ60_RECEPTACLE") (pin "P$19") (pinfunction "RTN_BATV_SW2_P$19") (pintype "power_in"))
      (node (ref "PQ60_RECEPTACLE") (pin "P$20") (pinfunction "RTN_BATV_SW2_P$20") (pintype "power_in"))
      (node (ref "PQ60_RECEPTACLE") (pin "P$23") (pinfunction "RTN_BATV_SW3_P$23") (pintype "power_in"))
      (node (ref "PQ60_RECEPTACLE") (pin "P$24") (pinfunction "RTN_BATV_SW3_P$24") (pintype "power_in"))
      (node (ref "PQ60_RECEPTACLE") (pin "P$28") (pinfunction "GND_P$28") (pintype "bidirectional"))
      (node (ref "PQ60_RECEPTACLE") (pin "P$3") (pinfunction "RTN_+3V3_SW1_P$3") (pintype "power_in"))
      (node (ref "PQ60_RECEPTACLE") (pin "P$4") (pinfunction "RTN_+3V3_SW1_P$4") (pintype "power_in"))
      (node (ref "PQ60_RECEPTACLE") (pin "P$45") (pinfunction "RTN_BATV_P$45") (pintype "power_in"))
      (node (ref "PQ60_RECEPTACLE") (pin "P$46") (pinfunction "RTN_BATV_P$46") (pintype "power_in"))
      (node (ref "PQ60_RECEPTACLE") (pin "P$47") (pinfunction "RTN_BATV_P$47") (pintype "power_in"))
      (node (ref "PQ60_RECEPTACLE") (pin "P$48") (pinfunction "RTN_BATV_P$48") (pintype "power_in"))
      (node (ref "PQ60_RECEPTACLE") (pin "P$53") (pinfunction "RTN_+3V3_P$53") (pintype "power_in"))
      (node (ref "PQ60_RECEPTACLE") (pin "P$54") (pinfunction "RTN_+3V3_P$54") (pintype "power_in"))
      (node (ref "PQ60_RECEPTACLE") (pin "P$55") (pinfunction "RTN_+3V3_P$55") (pintype "power_in"))
      (node (ref "PQ60_RECEPTACLE") (pin "P$56") (pinfunction "RTN_+3V3_P$56") (pintype "power_in"))
      (node (ref "PQ60_RECEPTACLE") (pin "P$7") (pinfunction "RTN_+3V3_SW2_P$7") (pintype "power_in"))
      (node (ref "PQ60_RECEPTACLE") (pin "P$8") (pinfunction "RTN_+3V3_SW2_P$8") (pintype "power_in"))
      (node (ref "R10") (pin "1") (pinfunction "1_1") (pintype "passive"))
      (node (ref "R11") (pin "1") (pinfunction "1_1") (pintype "passive"))
      (node (ref "R12") (pin "1") (pinfunction "1_1") (pintype "passive"))
      (node (ref "R14") (pin "1") (pinfunction "1_1") (pintype "passive"))
      (node (ref "R15") (pin "1") (pinfunction "1_1") (pintype "passive"))
      (node (ref "R16") (pin "1") (pinfunction "1_1") (pintype "passive"))
      (node (ref "R17") (pin "1") (pinfunction "1_1") (pintype "passive"))
      (node (ref "R2") (pin "1") (pinfunction "1_1") (pintype "passive"))
      (node (ref "R21") (pin "1") (pinfunction "1_1") (pintype "passive"))
      (node (ref "R23") (pin "1") (pinfunction "1_1") (pintype "passive"))
      (node (ref "R24") (pin "1") (pinfunction "1_1") (pintype "passive"))
      (node (ref "R25") (pin "1") (pinfunction "1_1") (pintype "passive"))
      (node (ref "R27") (pin "1") (pinfunction "1_1") (pintype "passive"))
      (node (ref "R29") (pin "1") (pinfunction "1_1") (pintype "passive"))
      (node (ref "R3") (pin "2") (pinfunction "2_2") (pintype "passive"))
      (node (ref "R34") (pin "2") (pinfunction "2_2") (pintype "passive"))
      (node (ref "R40") (pin "1") (pinfunction "1_1") (pintype "passive"))
      (node (ref "R5") (pin "1") (pinfunction "1_1") (pintype "passive"))
      (node (ref "R6") (pin "2") (pinfunction "2_2") (pintype "passive"))
      (node (ref "R7") (pin "2") (pinfunction "2_2") (pintype "passive"))
      (node (ref "R8") (pin "1") (pinfunction "1_1") (pintype "passive"))
      (node (ref "R9") (pin "1") (pinfunction "1_1") (pintype "passive"))
      (node (ref "SOL1") (pin "P$1") (pinfunction "-_P$1") (pintype "bidirectional"))
      (node (ref "SOL2") (pin "P$1") (pinfunction "-_P$1") (pintype "bidirectional"))
      (node (ref "SOL3") (pin "P$1") (pinfunction "-_P$1") (pintype "bidirectional"))
      (node (ref "SOL4") (pin "P$1") (pinfunction "-_P$1") (pintype "bidirectional"))
      (node (ref "STWD100") (pin "2") (pinfunction "GND_2") (pintype "bidirectional"))
      (node (ref "U$18") (pin "5") (pinfunction "GND_5") (pintype "bidirectional"))
      (node (ref "U$19") (pin "5") (pinfunction "GND_5") (pintype "bidirectional"))
      (node (ref "U$2") (pin "14") (pinfunction "TMR_14") (pintype "bidirectional"))
      (node (ref "U$2") (pin "15") (pinfunction "SYSOFF_15") (pintype "bidirectional"))
      (node (ref "U$2") (pin "17") (pinfunction "VSS_17") (pintype "bidirectional"))
      (node (ref "U$2") (pin "4") (pinfunction "CE_4") (pintype "bidirectional"))
      (node (ref "U$2") (pin "5") (pinfunction "EN2_5") (pintype "bidirectional"))
      (node (ref "U$2") (pin "7") (pinfunction "PGOOD_7") (pintype "bidirectional"))
      (node (ref "U$2") (pin "8") (pinfunction "VSS_8") (pintype "bidirectional"))
      (node (ref "U$2") (pin "9") (pinfunction "CHG_9") (pintype "bidirectional"))
      (node (ref "U$20") (pin "P$2") (pinfunction "GND_P$2") (pintype "bidirectional"))
      (node (ref "U$20") (pin "P$4") (pinfunction "GND_P$4") (pintype "bidirectional"))
      (node (ref "U$21") (pin "5") (pinfunction "VREFL_5") (pintype "bidirectional"))
      (node (ref "U$21") (pin "6") (pinfunction "VSS_6") (pintype "bidirectional"))
      (node (ref "U$21") (pin "GND@1") (pinfunction "VSS_GND@1") (pintype "bidirectional"))
      (node (ref "U$21") (pin "GND@2") (pinfunction "VSS_GND@2") (pintype "bidirectional"))
      (node (ref "U$21") (pin "GND@3") (pinfunction "VSS_GND@3") (pintype "bidirectional"))
      (node (ref "U$22") (pin "5") (pinfunction "GND_5") (pintype "bidirectional"))
      (node (ref "U$24") (pin "CATHODE") (pinfunction "CATHODE_CATHODE") (pintype "bidirectional"))
      (node (ref "U$24") (pin "EMITTER") (pinfunction "EMITTER_EMITTER") (pintype "bidirectional"))
      (node (ref "U$25") (pin "5") (pinfunction "GND_5") (pintype "bidirectional"))
      (node (ref "U$26") (pin "5") (pinfunction "GND_5") (pintype "bidirectional"))
      (node (ref "U$29") (pin "P$2") (pinfunction "SUB_P$2") (pintype "bidirectional"))
      (node (ref "U$29") (pin "P$4") (pinfunction "GND_P$4") (pintype "bidirectional"))
      (node (ref "U$3") (pin "P$2") (pinfunction "P$2_P$2") (pintype "bidirectional"))
      (node (ref "U1") (pin "11") (pinfunction "EP_11") (pintype "passive"))
      (node (ref "U1") (pin "2") (pinfunction "ENBA_2") (pintype "input"))
      (node (ref "U1") (pin "3") (pinfunction "GND_3") (pintype "passive"))
      (node (ref "U1") (pin "4") (pinfunction "ENBB_4") (pintype "input"))
      (node (ref "U1") (pin "9") (pinfunction "STAT_9") (pintype "output"))
      (node (ref "U10") (pin "6") (pinfunction "GND_6") (pintype "passive"))
      (node (ref "U10") (pin "7") (pinfunction "SR_7") (pintype "input"))
      (node (ref "U11") (pin "6") (pinfunction "GND_6") (pintype "passive"))
      (node (ref "U11") (pin "7") (pinfunction "SR_7") (pintype "input"))
      (node (ref "U12") (pin "6") (pinfunction "GND_6") (pintype "passive"))
      (node (ref "U12") (pin "7") (pinfunction "SR_7") (pintype "input"))
      (node (ref "U9") (pin "5") (pinfunction "GND_5") (pintype "passive"))
      (node (ref "U9") (pin "7") (pinfunction "EP_7") (pintype "passive"))
    )
    (net (code "23") (name "GPIO0") (class "Default")
      (node (ref "PQ60_HEADER") (pin "P$25") (pinfunction "GPIO0_P$25") (pintype "bidirectional"))
      (node (ref "PQ60_RECEPTACLE") (pin "P$25") (pinfunction "GPIO0_P$25") (pintype "bidirectional"))
      (node (ref "U$21") (pin "17") (pinfunction "PTB1_17") (pintype "bidirectional"))
    )
    (net (code "24") (name "GPIO1") (class "Default")
      (node (ref "PQ60_HEADER") (pin "P$26") (pinfunction "GPIO1_P$26") (pintype "bidirectional"))
      (node (ref "PQ60_RECEPTACLE") (pin "P$26") (pinfunction "GPIO1_P$26") (pintype "bidirectional"))
    )
    (net (code "25") (name "GPIO2") (class "Default")
      (node (ref "PQ60_HEADER") (pin "P$34") (pinfunction "/SS/GPIO2_P$34") (pintype "bidirectional"))
      (node (ref "PQ60_RECEPTACLE") (pin "P$34") (pinfunction "/SS/GPIO2_P$34") (pintype "bidirectional"))
    )
    (net (code "26") (name "GPIO3") (class "Default")
      (node (ref "PQ60_HEADER") (pin "P$35") (pinfunction "GPIO3_P$35") (pintype "bidirectional"))
      (node (ref "PQ60_RECEPTACLE") (pin "P$35") (pinfunction "GPIO3_P$35") (pintype "bidirectional"))
    )
    (net (code "27") (name "GPIO4") (class "Default")
      (node (ref "PQ60_HEADER") (pin "P$36") (pinfunction "GPIO4_P$36") (pintype "bidirectional"))
      (node (ref "PQ60_RECEPTACLE") (pin "P$36") (pinfunction "GPIO4_P$36") (pintype "bidirectional"))
    )
    (net (code "28") (name "GPIO5") (class "Default")
      (node (ref "PQ60_HEADER") (pin "P$37") (pinfunction "GPIO5_P$37") (pintype "bidirectional"))
      (node (ref "PQ60_RECEPTACLE") (pin "P$37") (pinfunction "GPIO5_P$37") (pintype "bidirectional"))
    )
    (net (code "29") (name "GPIO6") (class "Default")
      (node (ref "PQ60_HEADER") (pin "P$38") (pinfunction "GPIO6_P$38") (pintype "bidirectional"))
      (node (ref "PQ60_RECEPTACLE") (pin "P$38") (pinfunction "GPIO6_P$38") (pintype "bidirectional"))
    )
    (net (code "30") (name "GPIO7") (class "Default")
      (node (ref "PQ60_HEADER") (pin "P$39") (pinfunction "GPIO7_P$39") (pintype "bidirectional"))
      (node (ref "PQ60_RECEPTACLE") (pin "P$39") (pinfunction "GPIO7_P$39") (pintype "bidirectional"))
    )
    (net (code "31") (name "GPIO8") (class "Default")
      (node (ref "PQ60_HEADER") (pin "P$40") (pinfunction "GPIO8_P$40") (pintype "bidirectional"))
      (node (ref "PQ60_RECEPTACLE") (pin "P$40") (pinfunction "GPIO8_P$40") (pintype "bidirectional"))
    )
    (net (code "32") (name "GPIO9") (class "Default")
      (node (ref "PQ60_HEADER") (pin "P$41") (pinfunction "GPIO9_P$41") (pintype "bidirectional"))
      (node (ref "PQ60_RECEPTACLE") (pin "P$41") (pinfunction "GPIO9_P$41") (pintype "bidirectional"))
    )
    (net (code "33") (name "GPIO10") (class "Default")
      (node (ref "PQ60_HEADER") (pin "P$42") (pinfunction "GPIO10_P$42") (pintype "bidirectional"))
      (node (ref "PQ60_RECEPTACLE") (pin "P$42") (pinfunction "GPIO10_P$42") (pintype "bidirectional"))
    )
    (net (code "34") (name "GPIO11") (class "Default")
      (node (ref "PQ60_HEADER") (pin "P$43") (pinfunction "GPIO11_P$43") (pintype "bidirectional"))
      (node (ref "PQ60_RECEPTACLE") (pin "P$43") (pinfunction "GPIO11_P$43") (pintype "bidirectional"))
    )
    (net (code "35") (name "GPIO12") (class "Default")
      (node (ref "PQ60_HEADER") (pin "P$44") (pinfunction "GPIO12_P$44") (pintype "bidirectional"))
      (node (ref "PQ60_RECEPTACLE") (pin "P$44") (pinfunction "GPIO12_P$44") (pintype "bidirectional"))
    )
    (net (code "36") (name "MISO") (class "Default")
      (node (ref "PQ60_HEADER") (pin "P$32") (pinfunction "MISO_P$32") (pintype "bidirectional"))
      (node (ref "PQ60_RECEPTACLE") (pin "P$32") (pinfunction "MISO_P$32") (pintype "bidirectional"))
    )
    (net (code "37") (name "MOSI") (class "Default")
      (node (ref "PQ60_HEADER") (pin "P$31") (pinfunction "MOSI_P$31") (pintype "bidirectional"))
      (node (ref "PQ60_RECEPTACLE") (pin "P$31") (pinfunction "MOSI_P$31") (pintype "bidirectional"))
    )
    (net (code "38") (name "MPPT1") (class "Default")
      (node (ref "C2") (pin "1") (pinfunction "1_1") (pintype "passive"))
      (node (ref "MPPT1") (pin "9") (pinfunction "VOUT_9") (pintype "passive"))
      (node (ref "R1") (pin "2") (pinfunction "2_2") (pintype "passive"))
      (node (ref "U1") (pin "1") (pinfunction "INA_1") (pintype "power_in"))
    )
    (net (code "39") (name "MPPT2") (class "Default")
      (node (ref "C6") (pin "1") (pinfunction "1_1") (pintype "passive"))
      (node (ref "MPPT2") (pin "9") (pinfunction "VOUT_9") (pintype "passive"))
      (node (ref "R4") (pin "2") (pinfunction "2_2") (pintype "passive"))
      (node (ref "U1") (pin "5") (pinfunction "INB_5") (pintype "power_in"))
    )
    (net (code "40") (name "MPPTV_SENS") (class "Default")
      (node (ref "R26") (pin "1") (pinfunction "1_1") (pintype "passive"))
      (node (ref "R27") (pin "2") (pinfunction "2_2") (pintype "passive"))
      (node (ref "U$21") (pin "26") (pinfunction "PTA12_26") (pintype "bidirectional"))
    )
    (net (code "41") (name "MPPT_RAW") (class "Default")
      (node (ref "R13") (pin "1") (pinfunction "1_1") (pintype "passive"))
      (node (ref "R26") (pin "2") (pinfunction "2_2") (pintype "passive"))
      (node (ref "U$18") (pin "1") (pinfunction "VIN_1") (pintype "bidirectional"))
      (node (ref "U1") (pin "10") (pinfunction "OUTA_10") (pintype "output"))
      (node (ref "U1") (pin "6") (pinfunction "OUTB_6") (pintype "output"))
    )
    (net (code "42") (name "Net-(INA210-IN+)") (class "Default")
      (node (ref "C9") (pin "1") (pinfunction "1_1") (pintype "passive"))
      (node (ref "INA210") (pin "4") (pinfunction "IN+_4") (pintype "bidirectional"))
      (node (ref "R19") (pin "2") (pinfunction "2_2") (pintype "passive"))
      (node (ref "U$2") (pin "2") (pinfunction "BAT_2") (pintype "bidirectional"))
      (node (ref "U$2") (pin "3") (pinfunction "BAT_3") (pintype "bidirectional"))
    )
    (net (code "43") (name "Net-(INA210-IN-)") (class "Default")
      (node (ref "INA210") (pin "5") (pinfunction "IN-_5") (pintype "bidirectional"))
      (node (ref "R19") (pin "1") (pinfunction "1_1") (pintype "passive"))
      (node (ref "R22") (pin "2") (pinfunction "2_2") (pintype "passive"))
      (node (ref "U$19") (pin "1") (pinfunction "VIN_1") (pintype "bidirectional"))
      (node (ref "U$3") (pin "P$1") (pinfunction "P$1_P$1") (pintype "bidirectional"))
    )
    (net (code "44") (name "Net-(INA210-REF)") (class "Default")
      (node (ref "INA210") (pin "1") (pinfunction "REF_1") (pintype "bidirectional"))
      (node (ref "R20") (pin "1") (pinfunction "1_1") (pintype "passive"))
      (node (ref "R21") (pin "2") (pinfunction "2_2") (pintype "passive"))
    )
    (net (code "45") (name "Net-(IND1-1)") (class "Default")
      (node (ref "IND1") (pin "P$1") (pinfunction "1_P$1") (pintype "passive"))
      (node (ref "MPPT1") (pin "7") (pinfunction "SW_7") (pintype "passive"))
    )
    (net (code "46") (name "Net-(IND1-2)") (class "Default")
      (node (ref "C1") (pin "1") (pinfunction "1_1") (pintype "passive"))
      (node (ref "IND1") (pin "P$3") (pinfunction "2_P$3") (pintype "passive"))
      (node (ref "MPPT1") (pin "6") (pinfunction "VIN_6") (pintype "input"))
      (node (ref "U$31") (pin "P$1") (pinfunction "C_P$1") (pintype "passive"))
      (node (ref "U$32") (pin "P$1") (pinfunction "C_P$1") (pintype "passive"))
    )
    (net (code "47") (name "Net-(IND2-1)") (class "Default")
      (node (ref "IND2") (pin "P$1") (pinfunction "1_P$1") (pintype "passive"))
      (node (ref "MPPT2") (pin "7") (pinfunction "SW_7") (pintype "passive"))
    )
    (net (code "48") (name "Net-(IND2-2)") (class "Default")
      (node (ref "C5") (pin "1") (pinfunction "1_1") (pintype "passive"))
      (node (ref "IND2") (pin "P$3") (pinfunction "2_P$3") (pintype "passive"))
      (node (ref "MPPT2") (pin "6") (pinfunction "VIN_6") (pintype "input"))
      (node (ref "U$14") (pin "P$1") (pinfunction "C_P$1") (pintype "passive"))
      (node (ref "U$17") (pin "P$1") (pinfunction "C_P$1") (pintype "passive"))
    )
    (net (code "49") (name "Net-(MPPT1-AUX)") (class "Default")
      (node (ref "C3") (pin "1") (pinfunction "1_1") (pintype "passive"))
      (node (ref "MPPT1") (pin "10") (pinfunction "AUX_10") (pintype "passive"))
    )
    (net (code "50") (name "Net-(MPPT1-FB)") (class "Default")
      (node (ref "MPPT1") (pin "1") (pinfunction "FB_1") (pintype "passive"))
      (node (ref "R1") (pin "1") (pinfunction "1_1") (pintype "passive"))
      (node (ref "R2") (pin "2") (pinfunction "2_2") (pintype "passive"))
    )
    (net (code "51") (name "Net-(MPPT1-LDO)") (class "Default")
      (node (ref "C4") (pin "1") (pinfunction "1_1") (pintype "passive"))
      (node (ref "MPPT1") (pin "2") (pinfunction "LDO_2") (pintype "passive"))
    )
    (net (code "52") (name "Net-(MPPT1-MPPC)") (class "Default")
      (node (ref "MPPT1") (pin "5") (pinfunction "MPPC_5") (pintype "input"))
      (node (ref "R3") (pin "1") (pinfunction "1_1") (pintype "passive"))
    )
    (net (code "53") (name "Net-(MPPT1-SHDN)") (class "Default")
      (node (ref "MPPT1") (pin "4") (pinfunction "SHDN_4") (pintype "input"))
      (node (ref "U$4") (pin "P$2") (pinfunction "A_P$2") (pintype "passive"))
    )
    (net (code "54") (name "Net-(MPPT2-AUX)") (class "Default")
      (node (ref "C7") (pin "1") (pinfunction "1_1") (pintype "passive"))
      (node (ref "MPPT2") (pin "10") (pinfunction "AUX_10") (pintype "passive"))
    )
    (net (code "55") (name "Net-(MPPT2-FB)") (class "Default")
      (node (ref "MPPT2") (pin "1") (pinfunction "FB_1") (pintype "passive"))
      (node (ref "R4") (pin "1") (pinfunction "1_1") (pintype "passive"))
      (node (ref "R5") (pin "2") (pinfunction "2_2") (pintype "passive"))
    )
    (net (code "56") (name "Net-(MPPT2-LDO)") (class "Default")
      (node (ref "C8") (pin "1") (pinfunction "1_1") (pintype "passive"))
      (node (ref "MPPT2") (pin "2") (pinfunction "LDO_2") (pintype "passive"))
    )
    (net (code "57") (name "Net-(MPPT2-MPPC)") (class "Default")
      (node (ref "MPPT2") (pin "5") (pinfunction "MPPC_5") (pintype "input"))
      (node (ref "R6") (pin "1") (pinfunction "1_1") (pintype "passive"))
    )
    (net (code "58") (name "Net-(MPPT2-SHDN)") (class "Default")
      (node (ref "MPPT2") (pin "4") (pinfunction "SHDN_4") (pintype "input"))
      (node (ref "U$10") (pin "P$2") (pinfunction "A_P$2") (pintype "passive"))
    )
    (net (code "59") (name "Net-(R33-Pad2)") (class "Default")
      (node (ref "R33") (pin "2") (pinfunction "2_2") (pintype "passive"))
      (node (ref "U$24") (pin "ANODE") (pinfunction "ANODE_ANODE") (pintype "bidirectional"))
    )
    (net (code "60") (name "Net-(SOL1-+)") (class "Default")
      (node (ref "SOL1") (pin "P$2") (pinfunction "+_P$2") (pintype "bidirectional"))
      (node (ref "U$32") (pin "P$2") (pinfunction "A_P$2") (pintype "passive"))
    )
    (net (code "61") (name "Net-(SOL2-+)") (class "Default")
      (node (ref "SOL2") (pin "P$2") (pinfunction "+_P$2") (pintype "bidirectional"))
      (node (ref "U$31") (pin "P$2") (pinfunction "A_P$2") (pintype "passive"))
    )
    (net (code "62") (name "Net-(SOL3-+)") (class "Default")
      (node (ref "SOL3") (pin "P$2") (pinfunction "+_P$2") (pintype "bidirectional"))
      (node (ref "U$14") (pin "P$2") (pinfunction "A_P$2") (pintype "passive"))
    )
    (net (code "63") (name "Net-(SOL4-+)") (class "Default")
      (node (ref "SOL4") (pin "P$2") (pinfunction "+_P$2") (pintype "bidirectional"))
      (node (ref "U$17") (pin "P$2") (pinfunction "A_P$2") (pintype "passive"))
    )
    (net (code "64") (name "Net-(STWD100-EN)") (class "Default")
      (node (ref "R24") (pin "2") (pinfunction "2_2") (pintype "passive"))
      (node (ref "SJ1") (pin "2") (pinfunction "2_2") (pintype "passive"))
      (node (ref "STWD100") (pin "3") (pinfunction "EN_3") (pintype "bidirectional"))
    )
    (net (code "65") (name "Net-(U$1-EXTAL)") (class "Default")
      (node (ref "U$1") (pin "P$2") (pinfunction "EXTAL_P$2") (pintype "bidirectional"))
      (node (ref "U$21") (pin "7") (pinfunction "PTA3_7") (pintype "bidirectional"))
    )
    (net (code "66") (name "Net-(U$1-XTAL)") (class "Default")
      (node (ref "U$1") (pin "P$1") (pinfunction "XTAL_P$1") (pintype "bidirectional"))
      (node (ref "U$21") (pin "8") (pinfunction "PTA4_8") (pintype "bidirectional"))
    )
    (net (code "67") (name "Net-(U$2-ILIM)") (class "Default")
      (node (ref "R17") (pin "2") (pinfunction "2_2") (pintype "passive"))
      (node (ref "U$2") (pin "12") (pinfunction "ILIM_12") (pintype "bidirectional"))
    )
    (net (code "68") (name "Net-(U$2-ISET)") (class "Default")
      (node (ref "R16") (pin "2") (pinfunction "2_2") (pintype "passive"))
      (node (ref "U$2") (pin "16") (pinfunction "ISET_16") (pintype "bidirectional"))
    )
    (net (code "69") (name "Net-(U$2-TS)") (class "Default")
      (node (ref "R15") (pin "2") (pinfunction "2_2") (pintype "passive"))
      (node (ref "U$2") (pin "1") (pinfunction "TS_1") (pintype "bidirectional"))
    )
    (net (code "70") (name "Net-(U$20-VIN)") (class "Default")
      (node (ref "C14") (pin "1") (pinfunction "1_1") (pintype "passive"))
      (node (ref "U$20") (pin "P$1") (pinfunction "VIN_P$1") (pintype "bidirectional"))
      (node (ref "U9") (pin "1") (pinfunction "OUT_1") (pintype "output"))
    )
    (net (code "71") (name "Net-(U$20-VOUT)") (class "Default")
      (node (ref "C13") (pin "1") (pinfunction "1_1") (pintype "passive"))
      (node (ref "R36") (pin "1") (pinfunction "1_1") (pintype "passive"))
      (node (ref "R37") (pin "1") (pinfunction "1_1") (pintype "passive"))
      (node (ref "U$20") (pin "P$3") (pinfunction "VOUT_P$3") (pintype "bidirectional"))
      (node (ref "U$25") (pin "1") (pinfunction "VIN_1") (pintype "bidirectional"))
      (node (ref "U$26") (pin "1") (pinfunction "VIN_1") (pintype "bidirectional"))
    )
    (net (code "72") (name "Net-(U$21-PTB13)") (class "Default")
      (node (ref "R32") (pin "2") (pinfunction "2_2") (pintype "passive"))
      (node (ref "R34") (pin "1") (pinfunction "1_1") (pintype "passive"))
      (node (ref "U$21") (pin "29") (pinfunction "PTB13_29") (pintype "bidirectional"))
    )
    (net (code "73") (name "Net-(U9-ILIM)") (class "Default")
      (node (ref "R40") (pin "2") (pinfunction "2_2") (pintype "passive"))
      (node (ref "U9") (pin "2") (pinfunction "ILIM_2") (pintype "output"))
    )
    (net (code "74") (name "OPTO") (class "Default")
      (node (ref "R33") (pin "1") (pinfunction "1_1") (pintype "passive"))
      (node (ref "U$21") (pin "1") (pinfunction "PTB6_1") (pintype "bidirectional"))
    )
    (net (code "75") (name "SCK") (class "Default")
      (node (ref "PQ60_HEADER") (pin "P$33") (pinfunction "SCK_P$33") (pintype "bidirectional"))
      (node (ref "PQ60_RECEPTACLE") (pin "P$33") (pinfunction "SCK_P$33") (pintype "bidirectional"))
    )
    (net (code "76") (name "SCL") (class "Default")
      (node (ref "PQ60_HEADER") (pin "P$29") (pinfunction "SCL_P$29") (pintype "bidirectional"))
      (node (ref "PQ60_RECEPTACLE") (pin "P$29") (pinfunction "SCL_P$29") (pintype "bidirectional"))
      (node (ref "U$21") (pin "23") (pinfunction "PTB3_23") (pintype "bidirectional"))
    )
    (net (code "77") (name "SDA") (class "Default")
      (node (ref "PQ60_HEADER") (pin "P$30") (pinfunction "SDA_P$30") (pintype "bidirectional"))
      (node (ref "PQ60_RECEPTACLE") (pin "P$30") (pinfunction "SDA_P$30") (pintype "bidirectional"))
      (node (ref "U$21") (pin "24") (pinfunction "PTB4_24") (pintype "bidirectional"))
    )
    (net (code "78") (name "SHDN") (class "Default")
      (node (ref "U$10") (pin "P$1") (pinfunction "C_P$1") (pintype "passive"))
      (node (ref "U$24") (pin "COLLECTOR") (pinfunction "COLLECTOR_COLLECTOR") (pintype "bidirectional"))
      (node (ref "U$4") (pin "P$1") (pinfunction "C_P$1") (pintype "passive"))
    )
    (net (code "79") (name "SOL_ISEN") (class "Default")
      (node (ref "R8") (pin "2") (pinfunction "2_2") (pintype "passive"))
      (node (ref "U$18") (pin "3") (pinfunction "IOUT_3") (pintype "bidirectional"))
      (node (ref "U$21") (pin "13") (pinfunction "PTB10_13") (pintype "bidirectional"))
    )
    (net (code "80") (name "SWDCLK") (class "Default")
      (node (ref "U$21") (pin "30") (pinfunction "PTA0_30") (pintype "bidirectional"))
      (node (ref "U$22") (pin "4") (pinfunction "CLK_4") (pintype "bidirectional"))
    )
    (net (code "81") (name "SWDIO") (class "Default")
      (node (ref "U$21") (pin "32") (pinfunction "PTA2_32") (pintype "bidirectional"))
      (node (ref "U$22") (pin "2") (pinfunction "DIO_2") (pintype "bidirectional"))
    )
    (net (code "82") (name "SWDRST") (class "Default")
      (node (ref "U$21") (pin "31") (pinfunction "PTA1_31") (pintype "bidirectional"))
      (node (ref "U$22") (pin "3") (pinfunction "RST_3") (pintype "bidirectional"))
    )
    (net (code "83") (name "SYS") (class "Default")
      (node (ref "C10") (pin "1") (pinfunction "1_1") (pintype "passive"))
      (node (ref "PWR") (pin "PIN2") (pinfunction "PIN2_PIN2") (pintype "bidirectional"))
      (node (ref "U$2") (pin "10") (pinfunction "OUT_10") (pintype "bidirectional"))
      (node (ref "U$2") (pin "11") (pinfunction "OUT_11") (pintype "bidirectional"))
    )
    (net (code "84") (name "SYS_RAW") (class "Default")
      (node (ref "SJ1") (pin "1") (pinfunction "1_1") (pintype "passive"))
    )
    (net (code "85") (name "SYS_SW") (class "Default")
      (node (ref "PWR") (pin "PIN1") (pinfunction "PIN1_PIN1") (pintype "bidirectional"))
      (node (ref "R28") (pin "2") (pinfunction "2_2") (pintype "passive"))
      (node (ref "STWD100") (pin "5") (pinfunction "VCC_5") (pintype "bidirectional"))
      (node (ref "U$29") (pin "P$5") (pinfunction "VDD_P$5") (pintype "bidirectional"))
      (node (ref "U9") (pin "6") (pinfunction "IN_6") (pintype "power_in"))
    )
    (net (code "86") (name "USB_DISCONNECT") (class "Default")
      (node (ref "R30") (pin "1") (pinfunction "1_1") (pintype "passive"))
      (node (ref "U$21") (pin "9") (pinfunction "PTA5_9") (pintype "bidirectional"))
      (node (ref "U12") (pin "2") (pinfunction "ON1_2") (pintype "input"))
    )
    (net (code "87") (name "WDI") (class "Default")
      (node (ref "STWD100") (pin "4") (pinfunction "WDI_4") (pintype "bidirectional"))
      (node (ref "U$21") (pin "10") (pinfunction "PTA6_10") (pintype "bidirectional"))
    )
    (net (code "88") (name "unconnected-(MPPT1-PGOOD-Pad8)") (class "Default")
      (node (ref "MPPT1") (pin "8") (pinfunction "PGOOD_8") (pintype "passive"))
    )
    (net (code "89") (name "unconnected-(MPPT2-PGOOD-Pad8)") (class "Default")
      (node (ref "MPPT2") (pin "8") (pinfunction "PGOOD_8") (pintype "passive"))
    )
    (net (code "90") (name "unconnected-(U$1-GND-PadP$3)") (class "Default")
      (node (ref "U$1") (pin "P$3") (pinfunction "GND_P$3") (pintype "bidirectional"))
    )
    (net (code "91") (name "unconnected-(U$18-NC-Pad2)") (class "Default")
      (node (ref "U$18") (pin "2") (pinfunction "NC_2") (pintype "bidirectional"))
    )
    (net (code "92") (name "unconnected-(U$18-NC-Pad4)") (class "Default")
      (node (ref "U$18") (pin "4") (pinfunction "NC_4") (pintype "bidirectional"))
    )
    (net (code "93") (name "unconnected-(U$19-NC-Pad2)") (class "Default")
      (node (ref "U$19") (pin "2") (pinfunction "NC_2") (pintype "bidirectional"))
    )
    (net (code "94") (name "unconnected-(U$19-NC-Pad4)") (class "Default")
      (node (ref "U$19") (pin "4") (pinfunction "NC_4") (pintype "bidirectional"))
    )
    (net (code "95") (name "unconnected-(U$21-PTA13-Pad27)") (class "Default")
      (node (ref "U$21") (pin "27") (pinfunction "PTA13_27") (pintype "bidirectional"))
    )
    (net (code "96") (name "unconnected-(U$21-PTB11-Pad14)") (class "Default")
      (node (ref "U$21") (pin "14") (pinfunction "PTB11_14") (pintype "bidirectional"))
    )
    (net (code "97") (name "unconnected-(U$21-PTB12-Pad28)") (class "Default")
      (node (ref "U$21") (pin "28") (pinfunction "PTB12_28") (pintype "bidirectional"))
    )
    (net (code "98") (name "unconnected-(U$22-SWO-Pad6)") (class "Default")
      (node (ref "U$22") (pin "6") (pinfunction "SWO_6") (pintype "bidirectional"))
    )
    (net (code "99") (name "unconnected-(U$25-NC-Pad2)") (class "Default")
      (node (ref "U$25") (pin "2") (pinfunction "NC_2") (pintype "bidirectional"))
    )
    (net (code "100") (name "unconnected-(U$25-NC-Pad4)") (class "Default")
      (node (ref "U$25") (pin "4") (pinfunction "NC_4") (pintype "bidirectional"))
    )
    (net (code "101") (name "unconnected-(U$26-NC-Pad2)") (class "Default")
      (node (ref "U$26") (pin "2") (pinfunction "NC_2") (pintype "bidirectional"))
    )
    (net (code "102") (name "unconnected-(U$26-NC-Pad4)") (class "Default")
      (node (ref "U$26") (pin "4") (pinfunction "NC_4") (pintype "bidirectional"))
    )
    (net (code "103") (name "unconnected-(U$29-NC-PadP$3)") (class "Default")
      (node (ref "U$29") (pin "P$3") (pinfunction "NC_P$3") (pintype "bidirectional"))
    )
    (net (code "104") (name "unconnected-(U1-NC-Pad7)") (class "Default")
      (node (ref "U1") (pin "7") (pinfunction "NC_7") (pintype "no_connect"))
    )
    (net (code "105") (name "unconnected-(U1-NC_2-Pad8)") (class "Default")
      (node (ref "U1") (pin "8") (pinfunction "NC_2_8") (pintype "no_connect"))
    )
    (net (code "106") (name "unconnected-(U9-~{FAULT}-Pad3)") (class "Default")
      (node (ref "U9") (pin "3") (pinfunction "~{FAULT}_3") (pintype "output"))
    )
  )
)
